# NodeMCU_Base_Shield.net
KiCad netlist of a schematic drawn in EAGLE
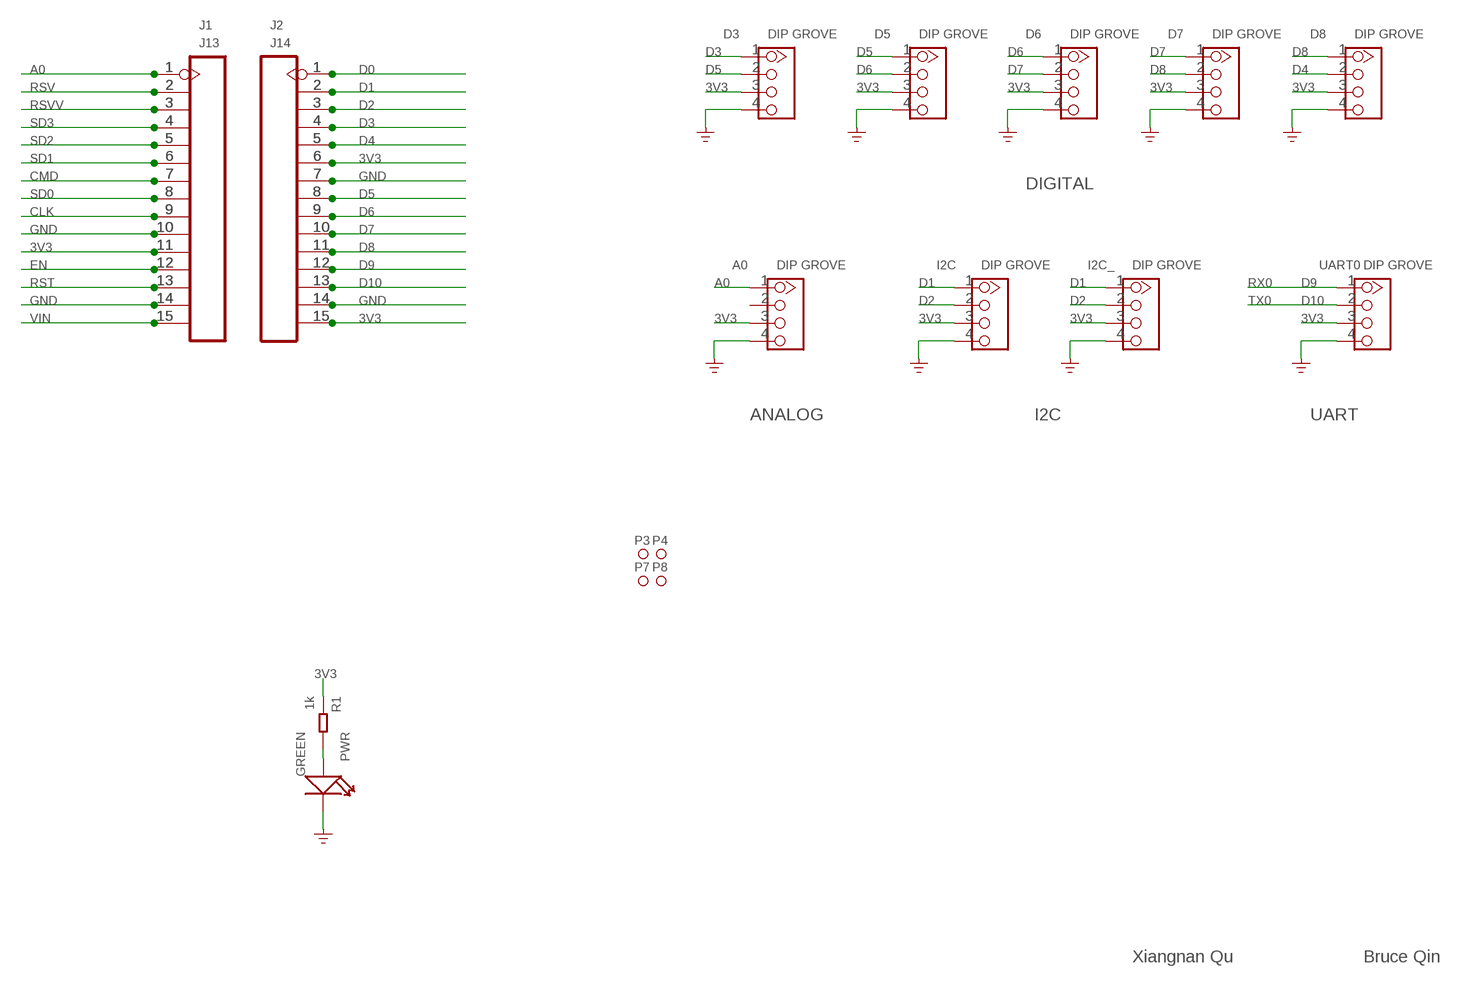
[diagram p0: schematic, sheet 1]

(export (version "E")
  (design (tool "Eeschema 10.0.6"))
  (components
    (comp (ref "A0")
      (value "DIP GROVE")
      (footprint "eagle-import:HW4-2.0")
      (libsource (lib "eagle-import") (part "GROVE-CONNECTOR-DIP-2.0"))
    )
    (comp (ref "D3")
      (value "DIP GROVE")
      (footprint "eagle-import:HW4-2.0")
      (libsource (lib "eagle-import") (part "GROVE-CONNECTOR-DIP-2.0"))
    )
    (comp (ref "D5")
      (value "DIP GROVE")
      (footprint "eagle-import:HW4-2.0")
      (libsource (lib "eagle-import") (part "GROVE-CONNECTOR-DIP-2.0"))
    )
    (comp (ref "D6")
      (value "DIP GROVE")
      (footprint "eagle-import:HW4-2.0")
      (libsource (lib "eagle-import") (part "GROVE-CONNECTOR-DIP-2.0"))
    )
    (comp (ref "D7")
      (value "DIP GROVE")
      (footprint "eagle-import:HW4-2.0")
      (libsource (lib "eagle-import") (part "GROVE-CONNECTOR-DIP-2.0"))
    )
    (comp (ref "D8")
      (value "DIP GROVE")
      (footprint "eagle-import:HW4-2.0")
      (libsource (lib "eagle-import") (part "GROVE-CONNECTOR-DIP-2.0"))
    )
    (comp (ref "I2C")
      (value "DIP GROVE")
      (footprint "eagle-import:HW4-2.0")
      (libsource (lib "eagle-import") (part "GROVE-CONNECTOR-DIP-2.0"))
    )
    (comp (ref "I2C_")
      (value "DIP GROVE")
      (footprint "eagle-import:HW4-2.0")
      (libsource (lib "eagle-import") (part "GROVE-CONNECTOR-DIP-2.0"))
    )
    (comp (ref "J1")
      (value "HEADER-15P'2.54'")
      (footprint "eagle-import:H15-2.54")
      (libsource (lib "eagle-import") (part "HEADER-15P'2.54'"))
    )
    (comp (ref "J2")
      (value "HEADER-15P'2.54'")
      (footprint "eagle-import:H15-2.54")
      (libsource (lib "eagle-import") (part "HEADER-15P'2.54'"))
    )
    (comp (ref "J13")
      (value "HEADER-15P'2.54'")
      (footprint "eagle-import:H15-2.54")
      (libsource (lib "eagle-import") (part "HEADER-15P'2.54'"))
    )
    (comp (ref "J14")
      (value "HEADER-15P'2.54'")
      (footprint "eagle-import:H15-2.54")
      (libsource (lib "eagle-import") (part "HEADER-15P'2.54'"))
    )
    (comp (ref "P3")
      (value "MARK-1.0'ANNULAR'")
      (footprint "eagle-import:ROUND-MARK-1.0")
      (fields (field (name "PARTNO") "DNP"))
      (libsource (lib "eagle-import") (part "MARK-1.0'ANNULAR'"))
    )
    (comp (ref "P4")
      (value "MARK-1.0'ANNULAR'")
      (footprint "eagle-import:ROUND-MARK-1.0")
      (fields (field (name "PARTNO") "DNP"))
      (libsource (lib "eagle-import") (part "MARK-1.0'ANNULAR'"))
    )
    (comp (ref "P7")
      (value "MARK-1.0'ANNULAR'")
      (footprint "eagle-import:ROUND-MARK-1.0")
      (fields (field (name "PARTNO") "DNP"))
      (libsource (lib "eagle-import") (part "MARK-1.0'ANNULAR'"))
    )
    (comp (ref "P8")
      (value "MARK-1.0'ANNULAR'")
      (footprint "eagle-import:ROUND-MARK-1.0")
      (fields (field (name "PARTNO") "DNP"))
      (libsource (lib "eagle-import") (part "MARK-1.0'ANNULAR'"))
    )
    (comp (ref "PWR")
      (value "GREEN")
      (footprint "eagle-import:LED-0603")
      (libsource (lib "eagle-import") (part "LED'0603'"))
    )
    (comp (ref "R1")
      (value "1k")
      (footprint "eagle-import:R0603")
      (libsource (lib "eagle-import") (part "RES-0603"))
    )
    (comp (ref "UART0")
      (value "DIP GROVE")
      (footprint "eagle-import:HW4-2.0")
      (libsource (lib "eagle-import") (part "GROVE-CONNECTOR-DIP-2.0"))
    )
  )
  (nets
    (net (code "1") (name "/3V3") (class "Default")
      (node (ref "A0") (pin "3") (pinfunction "3_3") (pintype "bidirectional"))
      (node (ref "D3") (pin "3") (pinfunction "3_3") (pintype "bidirectional"))
      (node (ref "D5") (pin "3") (pinfunction "3_3") (pintype "bidirectional"))
      (node (ref "D6") (pin "3") (pinfunction "3_3") (pintype "bidirectional"))
      (node (ref "D7") (pin "3") (pinfunction "3_3") (pintype "bidirectional"))
      (node (ref "D8") (pin "3") (pinfunction "3_3") (pintype "bidirectional"))
      (node (ref "I2C") (pin "3") (pinfunction "3_3") (pintype "bidirectional"))
      (node (ref "I2C_") (pin "3") (pinfunction "3_3") (pintype "bidirectional"))
      (node (ref "J1") (pin "11") (pinfunction "11_11") (pintype "passive"))
      (node (ref "J13") (pin "11") (pinfunction "11_11") (pintype "passive"))
      (node (ref "J14") (pin "15") (pinfunction "15_15") (pintype "passive"))
      (node (ref "J14") (pin "6") (pinfunction "6_6") (pintype "passive"))
      (node (ref "J2") (pin "15") (pinfunction "15_15") (pintype "passive"))
      (node (ref "J2") (pin "6") (pinfunction "6_6") (pintype "passive"))
      (node (ref "R1") (pin "1") (pinfunction "1_1") (pintype "passive"))
      (node (ref "UART0") (pin "3") (pinfunction "3_3") (pintype "bidirectional"))
    )
    (net (code "2") (name "/A0") (class "Default")
      (node (ref "A0") (pin "1") (pinfunction "1_1") (pintype "bidirectional"))
      (node (ref "J1") (pin "1") (pinfunction "1_1") (pintype "passive"))
      (node (ref "J13") (pin "1") (pinfunction "1_1") (pintype "passive"))
    )
    (net (code "3") (name "/CLK") (class "Default")
      (node (ref "J1") (pin "9") (pinfunction "9_9") (pintype "passive"))
      (node (ref "J13") (pin "9") (pinfunction "9_9") (pintype "passive"))
    )
    (net (code "4") (name "/CMD") (class "Default")
      (node (ref "J1") (pin "7") (pinfunction "7_7") (pintype "passive"))
      (node (ref "J13") (pin "7") (pinfunction "7_7") (pintype "passive"))
    )
    (net (code "5") (name "/D0") (class "Default")
      (node (ref "J14") (pin "1") (pinfunction "1_1") (pintype "passive"))
      (node (ref "J2") (pin "1") (pinfunction "1_1") (pintype "passive"))
    )
    (net (code "6") (name "/D1") (class "Default")
      (node (ref "I2C") (pin "1") (pinfunction "1_1") (pintype "bidirectional"))
      (node (ref "I2C_") (pin "1") (pinfunction "1_1") (pintype "bidirectional"))
      (node (ref "J14") (pin "2") (pinfunction "2_2") (pintype "passive"))
      (node (ref "J2") (pin "2") (pinfunction "2_2") (pintype "passive"))
    )
    (net (code "7") (name "/D2") (class "Default")
      (node (ref "I2C") (pin "2") (pinfunction "2_2") (pintype "bidirectional"))
      (node (ref "I2C_") (pin "2") (pinfunction "2_2") (pintype "bidirectional"))
      (node (ref "J14") (pin "3") (pinfunction "3_3") (pintype "passive"))
      (node (ref "J2") (pin "3") (pinfunction "3_3") (pintype "passive"))
    )
    (net (code "8") (name "/D3") (class "Default")
      (node (ref "D3") (pin "1") (pinfunction "1_1") (pintype "bidirectional"))
      (node (ref "J14") (pin "4") (pinfunction "4_4") (pintype "passive"))
      (node (ref "J2") (pin "4") (pinfunction "4_4") (pintype "passive"))
    )
    (net (code "9") (name "/D4") (class "Default")
      (node (ref "D8") (pin "2") (pinfunction "2_2") (pintype "bidirectional"))
      (node (ref "J14") (pin "5") (pinfunction "5_5") (pintype "passive"))
      (node (ref "J2") (pin "5") (pinfunction "5_5") (pintype "passive"))
    )
    (net (code "10") (name "/D5") (class "Default")
      (node (ref "D3") (pin "2") (pinfunction "2_2") (pintype "bidirectional"))
      (node (ref "D5") (pin "1") (pinfunction "1_1") (pintype "bidirectional"))
      (node (ref "J14") (pin "8") (pinfunction "8_8") (pintype "passive"))
      (node (ref "J2") (pin "8") (pinfunction "8_8") (pintype "passive"))
    )
    (net (code "11") (name "/D6") (class "Default")
      (node (ref "D5") (pin "2") (pinfunction "2_2") (pintype "bidirectional"))
      (node (ref "D6") (pin "1") (pinfunction "1_1") (pintype "bidirectional"))
      (node (ref "J14") (pin "9") (pinfunction "9_9") (pintype "passive"))
      (node (ref "J2") (pin "9") (pinfunction "9_9") (pintype "passive"))
    )
    (net (code "12") (name "/D7") (class "Default")
      (node (ref "D6") (pin "2") (pinfunction "2_2") (pintype "bidirectional"))
      (node (ref "D7") (pin "1") (pinfunction "1_1") (pintype "bidirectional"))
      (node (ref "J14") (pin "10") (pinfunction "10_10") (pintype "passive"))
      (node (ref "J2") (pin "10") (pinfunction "10_10") (pintype "passive"))
    )
    (net (code "13") (name "/D8") (class "Default")
      (node (ref "D7") (pin "2") (pinfunction "2_2") (pintype "bidirectional"))
      (node (ref "D8") (pin "1") (pinfunction "1_1") (pintype "bidirectional"))
      (node (ref "J14") (pin "11") (pinfunction "11_11") (pintype "passive"))
      (node (ref "J2") (pin "11") (pinfunction "11_11") (pintype "passive"))
    )
    (net (code "14") (name "/D9") (class "Default")
      (node (ref "J14") (pin "12") (pinfunction "12_12") (pintype "passive"))
      (node (ref "J2") (pin "12") (pinfunction "12_12") (pintype "passive"))
      (node (ref "UART0") (pin "1") (pinfunction "1_1") (pintype "bidirectional"))
    )
    (net (code "15") (name "/D10") (class "Default")
      (node (ref "J14") (pin "13") (pinfunction "13_13") (pintype "passive"))
      (node (ref "J2") (pin "13") (pinfunction "13_13") (pintype "passive"))
      (node (ref "UART0") (pin "2") (pinfunction "2_2") (pintype "bidirectional"))
    )
    (net (code "16") (name "/EN") (class "Default")
      (node (ref "J1") (pin "12") (pinfunction "12_12") (pintype "passive"))
      (node (ref "J13") (pin "12") (pinfunction "12_12") (pintype "passive"))
    )
    (net (code "17") (name "/RST") (class "Default")
      (node (ref "J1") (pin "13") (pinfunction "13_13") (pintype "passive"))
      (node (ref "J13") (pin "13") (pinfunction "13_13") (pintype "passive"))
    )
    (net (code "18") (name "/RSV") (class "Default")
      (node (ref "J1") (pin "2") (pinfunction "2_2") (pintype "passive"))
      (node (ref "J13") (pin "2") (pinfunction "2_2") (pintype "passive"))
    )
    (net (code "19") (name "/RSVV") (class "Default")
      (node (ref "J1") (pin "3") (pinfunction "3_3") (pintype "passive"))
      (node (ref "J13") (pin "3") (pinfunction "3_3") (pintype "passive"))
    )
    (net (code "20") (name "/SD0") (class "Default")
      (node (ref "J1") (pin "8") (pinfunction "8_8") (pintype "passive"))
      (node (ref "J13") (pin "8") (pinfunction "8_8") (pintype "passive"))
    )
    (net (code "21") (name "/SD1") (class "Default")
      (node (ref "J1") (pin "6") (pinfunction "6_6") (pintype "passive"))
      (node (ref "J13") (pin "6") (pinfunction "6_6") (pintype "passive"))
    )
    (net (code "22") (name "/SD2") (class "Default")
      (node (ref "J1") (pin "5") (pinfunction "5_5") (pintype "passive"))
      (node (ref "J13") (pin "5") (pinfunction "5_5") (pintype "passive"))
    )
    (net (code "23") (name "/SD3") (class "Default")
      (node (ref "J1") (pin "4") (pinfunction "4_4") (pintype "passive"))
      (node (ref "J13") (pin "4") (pinfunction "4_4") (pintype "passive"))
    )
    (net (code "24") (name "/VIN") (class "Default")
      (node (ref "J1") (pin "15") (pinfunction "15_15") (pintype "passive"))
      (node (ref "J13") (pin "15") (pinfunction "15_15") (pintype "passive"))
    )
    (net (code "25") (name "GND_POWER") (class "Default")
      (node (ref "A0") (pin "4") (pinfunction "4_4") (pintype "bidirectional"))
      (node (ref "D3") (pin "4") (pinfunction "4_4") (pintype "bidirectional"))
      (node (ref "D5") (pin "4") (pinfunction "4_4") (pintype "bidirectional"))
      (node (ref "D6") (pin "4") (pinfunction "4_4") (pintype "bidirectional"))
      (node (ref "D7") (pin "4") (pinfunction "4_4") (pintype "bidirectional"))
      (node (ref "D8") (pin "4") (pinfunction "4_4") (pintype "bidirectional"))
      (node (ref "I2C") (pin "4") (pinfunction "4_4") (pintype "bidirectional"))
      (node (ref "I2C_") (pin "4") (pinfunction "4_4") (pintype "bidirectional"))
      (node (ref "J1") (pin "10") (pinfunction "10_10") (pintype "passive"))
      (node (ref "J1") (pin "14") (pinfunction "14_14") (pintype "passive"))
      (node (ref "J13") (pin "10") (pinfunction "10_10") (pintype "passive"))
      (node (ref "J13") (pin "14") (pinfunction "14_14") (pintype "passive"))
      (node (ref "J14") (pin "14") (pinfunction "14_14") (pintype "passive"))
      (node (ref "J14") (pin "7") (pinfunction "7_7") (pintype "passive"))
      (node (ref "J2") (pin "14") (pinfunction "14_14") (pintype "passive"))
      (node (ref "J2") (pin "7") (pinfunction "7_7") (pintype "passive"))
      (node (ref "PWR") (pin "-") (pinfunction "-_-") (pintype "passive"))
      (node (ref "UART0") (pin "4") (pinfunction "4_4") (pintype "bidirectional"))
    )
    (net (code "26") (name "Net-(PWR-Pad+)") (class "Default")
      (node (ref "PWR") (pin "+") (pinfunction "+_+") (pintype "passive"))
      (node (ref "R1") (pin "2") (pinfunction "2_2") (pintype "passive"))
    )
    (net (code "27") (name "unconnected-(A0-Pad2)") (class "Default")
      (node (ref "A0") (pin "2") (pinfunction "2_2") (pintype "bidirectional"))
    )
  )
)
